# Power.net
KiCad netlist of a schematic drawn in Altium Designer
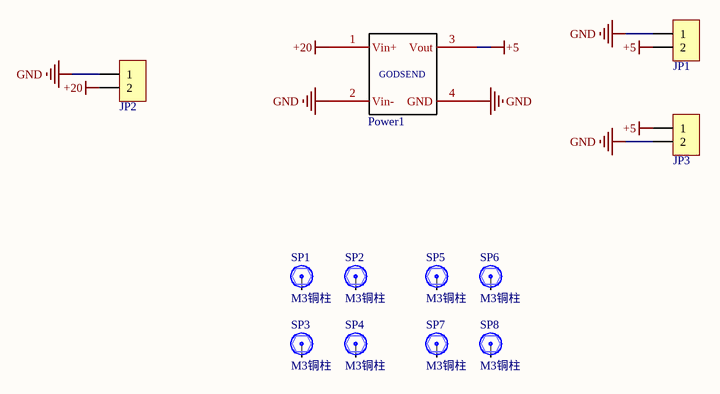
[diagram p0: Power.SchDoc]

(export (version "E")
  (design (tool "Eeschema 10.0.6"))
  (components
    (comp (ref "JP1")
      (value "HDR-1X2")
      (footprint "KF301-5.0-2P")
      (description "2P接插件")
      (fields (field (name "版权归属") "源创客"))
      (libsource (lib "4.9   - 接插件-脚距5.0") (part "Header 2"))
    )
    (comp (ref "JP2")
      (value "HDR-1X2")
      (footprint "KF301-5.0-2P")
      (description "2P接插件")
      (fields (field (name "版权归属") "源创客"))
      (libsource (lib "4.9   - 接插件-脚距5.0") (part "Header 2"))
    )
    (comp (ref "JP3")
      (value "HDR-1X2")
      (footprint "KF301-5.0-2P")
      (description "2P接插件")
      (fields (field (name "版权归属") "源创客"))
      (libsource (lib "4.9   - 接插件-脚距5.0") (part "Header 2"))
    )
    (comp (ref "Power1")
      (value "GODSEND")
      (footprint "GODSEND")
      (libsource (lib "HenryLib") (part "GODSEND"))
    )
    (comp (ref "SP1")
      (value "M3铜柱")
      (footprint "M3x10_L")
      (description "铜柱")
      (fields (field (name "版权归属") "源创客"))
      (libsource (lib "15.1 - 未分类器件") (part "铜柱小焊盘"))
    )
    (comp (ref "SP2")
      (value "M3铜柱")
      (footprint "M3x10_L")
      (description "铜柱")
      (fields (field (name "版权归属") "源创客"))
      (libsource (lib "15.1 - 未分类器件") (part "铜柱小焊盘"))
    )
    (comp (ref "SP3")
      (value "M3铜柱")
      (footprint "M3x10_L")
      (description "铜柱")
      (fields (field (name "版权归属") "源创客"))
      (libsource (lib "15.1 - 未分类器件") (part "铜柱小焊盘"))
    )
    (comp (ref "SP4")
      (value "M3铜柱")
      (footprint "M3x10_L")
      (description "铜柱")
      (fields (field (name "版权归属") "源创客"))
      (libsource (lib "15.1 - 未分类器件") (part "铜柱小焊盘"))
    )
    (comp (ref "SP5")
      (value "M3铜柱")
      (footprint "M3x10_L")
      (description "铜柱")
      (fields (field (name "版权归属") "源创客"))
      (libsource (lib "15.1 - 未分类器件") (part "铜柱小焊盘"))
    )
    (comp (ref "SP6")
      (value "M3铜柱")
      (footprint "M3x10_L")
      (description "铜柱")
      (fields (field (name "版权归属") "源创客"))
      (libsource (lib "15.1 - 未分类器件") (part "铜柱小焊盘"))
    )
    (comp (ref "SP7")
      (value "M3铜柱")
      (footprint "M3x10_L")
      (description "铜柱")
      (fields (field (name "版权归属") "源创客"))
      (libsource (lib "15.1 - 未分类器件") (part "铜柱小焊盘"))
    )
    (comp (ref "SP8")
      (value "M3铜柱")
      (footprint "M3x10_L")
      (description "铜柱")
      (fields (field (name "版权归属") "源创客"))
      (libsource (lib "15.1 - 未分类器件") (part "铜柱小焊盘"))
    )
  )
  (nets
    (net (code "1") (name "+5") (class "Default")
      (node (ref "JP1") (pin "2") (pinfunction "2_2") (pintype "passive"))
      (node (ref "JP3") (pin "1") (pinfunction "1_1") (pintype "passive"))
      (node (ref "Power1") (pin "3") (pinfunction "Vout_3") (pintype "passive"))
    )
    (net (code "2") (name "+20") (class "Default")
      (node (ref "JP2") (pin "2") (pinfunction "2_2") (pintype "passive"))
      (node (ref "Power1") (pin "1") (pinfunction "Vin+_1") (pintype "passive"))
    )
    (net (code "3") (name "GND") (class "Default")
      (node (ref "JP1") (pin "1") (pinfunction "1_1") (pintype "passive"))
      (node (ref "JP2") (pin "1") (pinfunction "1_1") (pintype "passive"))
      (node (ref "JP3") (pin "2") (pinfunction "2_2") (pintype "passive"))
      (node (ref "Power1") (pin "2") (pinfunction "Vin-_2") (pintype "passive"))
      (node (ref "Power1") (pin "4") (pinfunction "GND_4") (pintype "passive"))
    )
    (net (code "4") (name "unconnected-(SP1-Pad1)") (class "Default")
      (node (ref "SP1") (pin "1") (pinfunction "1_1") (pintype "passive"))
    )
    (net (code "5") (name "unconnected-(SP2-Pad1)") (class "Default")
      (node (ref "SP2") (pin "1") (pinfunction "1_1") (pintype "passive"))
    )
    (net (code "6") (name "unconnected-(SP3-Pad1)") (class "Default")
      (node (ref "SP3") (pin "1") (pinfunction "1_1") (pintype "passive"))
    )
    (net (code "7") (name "unconnected-(SP4-Pad1)") (class "Default")
      (node (ref "SP4") (pin "1") (pinfunction "1_1") (pintype "passive"))
    )
    (net (code "8") (name "unconnected-(SP5-Pad1)") (class "Default")
      (node (ref "SP5") (pin "1") (pinfunction "1_1") (pintype "passive"))
    )
    (net (code "9") (name "unconnected-(SP6-Pad1)") (class "Default")
      (node (ref "SP6") (pin "1") (pinfunction "1_1") (pintype "passive"))
    )
    (net (code "10") (name "unconnected-(SP7-Pad1)") (class "Default")
      (node (ref "SP7") (pin "1") (pinfunction "1_1") (pintype "passive"))
    )
    (net (code "11") (name "unconnected-(SP8-Pad1)") (class "Default")
      (node (ref "SP8") (pin "1") (pinfunction "1_1") (pintype "passive"))
    )
  )
)
